# RingerPro2.net
KiCad netlist of a schematic drawn in EAGLE
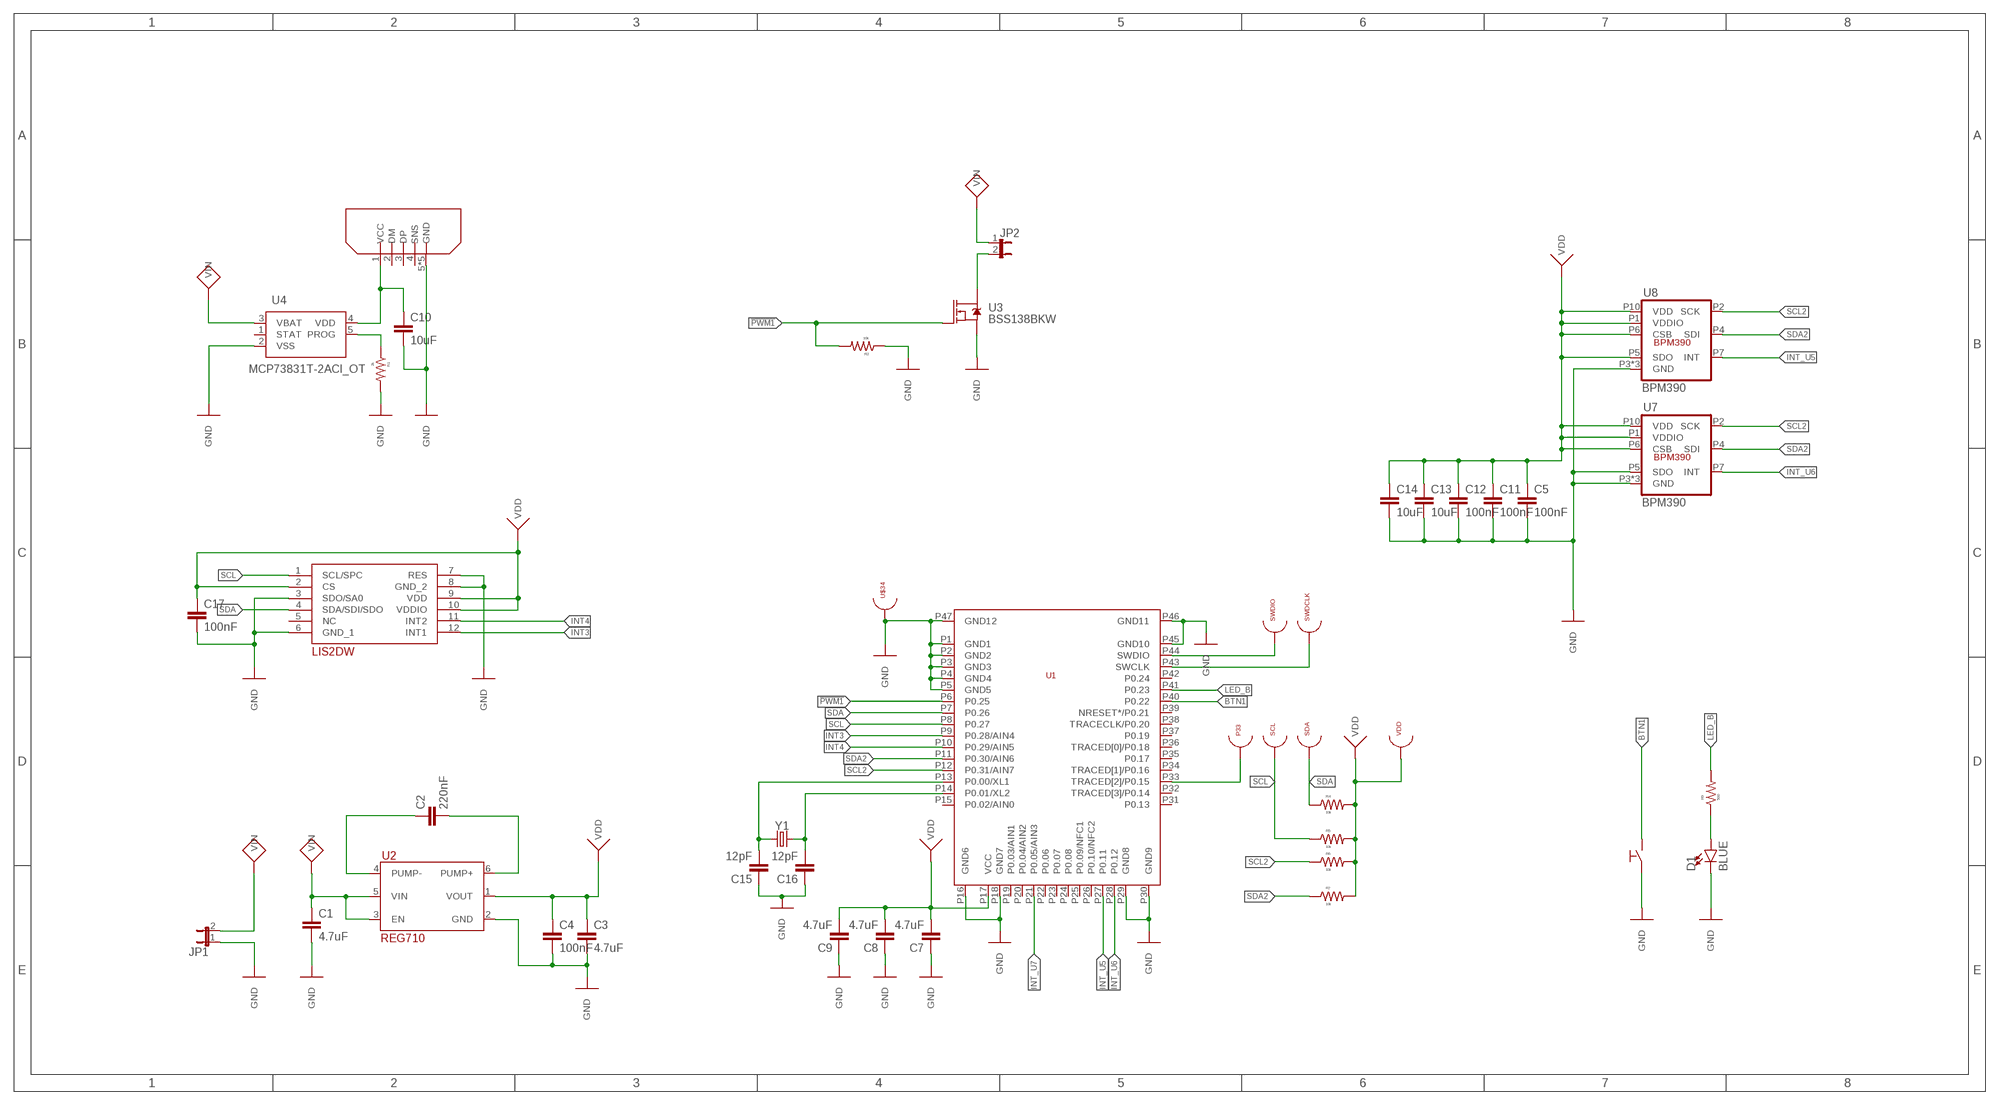
[diagram p0: schematic, sheet 1]

(export (version "E")
  (design (tool "Eeschema 10.0.6"))
  (components
    (comp (ref "C1")
      (value "4.7uF")
      (footprint "eagle-import:C0603")
      (libsource (lib "eagle-import") (part "CAPACITOR0603"))
    )
    (comp (ref "C2")
      (value "220nF")
      (footprint "eagle-import:C0603")
      (libsource (lib "eagle-import") (part "CAPACITOR0603"))
    )
    (comp (ref "C3")
      (value "4.7uF")
      (footprint "eagle-import:C0603")
      (libsource (lib "eagle-import") (part "CAPACITOR0603"))
    )
    (comp (ref "C4")
      (value "100nF")
      (footprint "eagle-import:C0603")
      (libsource (lib "eagle-import") (part "CAPACITOR0603"))
    )
    (comp (ref "C5")
      (value "100nF")
      (footprint "eagle-import:C0603")
      (libsource (lib "eagle-import") (part "CAPACITOR0603"))
    )
    (comp (ref "C7")
      (value "4.7uF")
      (footprint "eagle-import:C0603")
      (libsource (lib "eagle-import") (part "CAPACITOR0603"))
    )
    (comp (ref "C8")
      (value "4.7uF")
      (footprint "eagle-import:C0603")
      (libsource (lib "eagle-import") (part "CAPACITOR0603"))
    )
    (comp (ref "C9")
      (value "4.7uF")
      (footprint "eagle-import:C0603")
      (libsource (lib "eagle-import") (part "CAPACITOR0603"))
    )
    (comp (ref "C10")
      (value "10uF")
      (footprint "eagle-import:C0603")
      (libsource (lib "eagle-import") (part "CAPACITOR0603"))
    )
    (comp (ref "C11")
      (value "100nF")
      (footprint "eagle-import:C0603")
      (libsource (lib "eagle-import") (part "CAPACITOR0603"))
    )
    (comp (ref "C12")
      (value "100nF")
      (footprint "eagle-import:C0603")
      (libsource (lib "eagle-import") (part "CAPACITOR0603"))
    )
    (comp (ref "C13")
      (value "10uF")
      (footprint "eagle-import:C0603")
      (libsource (lib "eagle-import") (part "CAPACITOR0603"))
    )
    (comp (ref "C14")
      (value "10uF")
      (footprint "eagle-import:C0603")
      (libsource (lib "eagle-import") (part "CAPACITOR0603"))
    )
    (comp (ref "C15")
      (value "12pF")
      (footprint "eagle-import:C0603")
      (libsource (lib "eagle-import") (part "CAPACITOR0603"))
    )
    (comp (ref "C16")
      (value "12pF")
      (footprint "eagle-import:C0603")
      (libsource (lib "eagle-import") (part "CAPACITOR0603"))
    )
    (comp (ref "C17")
      (value "100nF")
      (footprint "eagle-import:C0603")
      (libsource (lib "eagle-import") (part "CAPACITOR0603"))
    )
    (comp (ref "D1")
      (value "BLUE")
      (footprint "eagle-import:LED-0603")
      (libsource (lib "eagle-import") (part "LED-BLUE0603"))
    )
    (comp (ref "IC1")
      (value "LIS2DW12TR")
      (footprint "eagle-import:LGA-12")
      (fields (field (name "MOUSER_PART_NUMBER") "511-LIS2DW12TR"))
      (libsource (lib "eagle-import") (part "LIS2DW12TR"))
    )
    (comp (ref "JP1")
      (value "JP1E")
      (footprint "eagle-import:JP1")
      (libsource (lib "eagle-import") (part "JP1E"))
    )
    (comp (ref "JP2")
      (value "JP1E")
      (footprint "eagle-import:JP1")
      (libsource (lib "eagle-import") (part "JP1E"))
    )
    (comp (ref "P33")
      (value "TESTPOINT_22")
      (footprint "eagle-import:TESTPOINT_22")
      (libsource (lib "eagle-import") (part "TESTPOINT_22"))
    )
    (comp (ref "R1")
      (value "2k")
      (footprint "eagle-import:R0603")
      (libsource (lib "eagle-import") (part "RESISTOR0603"))
    )
    (comp (ref "R2")
      (value "10k")
      (footprint "eagle-import:R0603")
      (libsource (lib "eagle-import") (part "RESISTOR0603"))
    )
    (comp (ref "R4")
      (value "10k")
      (footprint "eagle-import:R0603")
      (libsource (lib "eagle-import") (part "RESISTOR0603"))
    )
    (comp (ref "R5")
      (value "10k")
      (footprint "eagle-import:R0603")
      (libsource (lib "eagle-import") (part "RESISTOR0603"))
    )
    (comp (ref "R6")
      (value "10k")
      (footprint "eagle-import:R0603")
      (libsource (lib "eagle-import") (part "RESISTOR0603"))
    )
    (comp (ref "R7")
      (value "10k")
      (footprint "eagle-import:R0603")
      (libsource (lib "eagle-import") (part "RESISTOR0603"))
    )
    (comp (ref "R9")
      (value "500")
      (footprint "eagle-import:R0603")
      (libsource (lib "eagle-import") (part "RESISTOR0603"))
    )
    (comp (ref "SCL")
      (value "TESTPOINT_22")
      (footprint "eagle-import:TESTPOINT_22")
      (libsource (lib "eagle-import") (part "TESTPOINT_22"))
    )
    (comp (ref "SDA")
      (value "TESTPOINT_22")
      (footprint "eagle-import:TESTPOINT_22")
      (libsource (lib "eagle-import") (part "TESTPOINT_22"))
    )
    (comp (ref "SPST1")
      (value "PTS526SK08")
      (footprint "eagle-import:PTS526SKG15SMTR2LFS")
      (libsource (lib "eagle-import") (part "PTS526SK08"))
    )
    (comp (ref "SWDCLK")
      (value "TESTPOINT_22")
      (footprint "eagle-import:TESTPOINT_22")
      (libsource (lib "eagle-import") (part "TESTPOINT_22"))
    )
    (comp (ref "SWDIO")
      (value "TESTPOINT_22")
      (footprint "eagle-import:TESTPOINT_22")
      (libsource (lib "eagle-import") (part "TESTPOINT_22"))
    )
    (comp (ref "U$23")
      (value "ZX80B5P")
      (footprint "eagle-import:ZX80B5P")
      (libsource (lib "eagle-import") (part "ZX80B5P"))
    )
    (comp (ref "U$34")
      (value "TESTPOINT_22")
      (footprint "eagle-import:TESTPOINT_22")
      (libsource (lib "eagle-import") (part "TESTPOINT_22"))
    )
    (comp (ref "U1")
      (value "BMD-300")
      (footprint "eagle-import:BMD-300")
      (libsource (lib "eagle-import") (part "BMD-300"))
    )
    (comp (ref "U2")
      (value "REG710")
      (footprint "eagle-import:SOT457")
      (libsource (lib "eagle-import") (part "REG710"))
    )
    (comp (ref "U3")
      (value "BSS138BKW")
      (footprint "eagle-import:SOT65P210X110-3N")
      (libsource (lib "eagle-import") (part "BSS138BKW"))
    )
    (comp (ref "U4")
      (value "MCP73831T-2ACI_OT")
      (footprint "eagle-import:SOT95P270X145-5N")
      (fields
        (field (name "MANUFACTURER_PART_NUMBER") "MCP73831T-2ACI/OT")
        (field (name "MOUSER_PART_NUMBER") "579-MCP73831T-2ACIOT")
      )
      (libsource (lib "eagle-import") (part "MCP73831T-2ACI_OT"))
    )
    (comp (ref "U7")
      (value "BPM390")
      (footprint "eagle-import:BPM390")
      (libsource (lib "eagle-import") (part "BPM390"))
    )
    (comp (ref "U8")
      (value "BPM390")
      (footprint "eagle-import:BPM390")
      (libsource (lib "eagle-import") (part "BPM390"))
    )
    (comp (ref "VDD")
      (value "TESTPOINT_22")
      (footprint "eagle-import:TESTPOINT_22")
      (libsource (lib "eagle-import") (part "TESTPOINT_22"))
    )
    (comp (ref "Y1")
      (value "CRYSTALSMD-3.2X1.5")
      (footprint "eagle-import:CRYSTAL-SMD-3.2X1.5MM")
      (libsource (lib "eagle-import") (part "CRYSTALSMD-3.2X1.5"))
    )
  )
  (nets
    (net (code "1") (name "/~{PWM1}") (class "Default")
      (node (ref "R2") (pin "2") (pinfunction "2_2") (pintype "passive"))
      (node (ref "U1") (pin "P6") (pinfunction "P0.25_P6") (pintype "bidirectional"))
      (node (ref "U3") (pin "1") (pinfunction "G_1") (pintype "bidirectional"))
    )
    (net (code "2") (name "BTN1") (class "Default")
      (node (ref "SPST1") (pin "3") (pinfunction "P$2_3") (pintype "passive"))
      (node (ref "SPST1") (pin "4") (pinfunction "P$2_4") (pintype "passive"))
      (node (ref "U1") (pin "P40") (pinfunction "P0.22_P40") (pintype "bidirectional"))
    )
    (net (code "3") (name "GND") (class "Default")
      (node (ref "C1") (pin "2") (pinfunction "2_2") (pintype "passive"))
      (node (ref "C10") (pin "2") (pinfunction "2_2") (pintype "passive"))
      (node (ref "C11") (pin "2") (pinfunction "2_2") (pintype "passive"))
      (node (ref "C12") (pin "2") (pinfunction "2_2") (pintype "passive"))
      (node (ref "C13") (pin "2") (pinfunction "2_2") (pintype "passive"))
      (node (ref "C14") (pin "2") (pinfunction "2_2") (pintype "passive"))
      (node (ref "C15") (pin "1") (pinfunction "1_1") (pintype "passive"))
      (node (ref "C16") (pin "1") (pinfunction "1_1") (pintype "passive"))
      (node (ref "C17") (pin "2") (pinfunction "2_2") (pintype "passive"))
      (node (ref "C3") (pin "2") (pinfunction "2_2") (pintype "passive"))
      (node (ref "C4") (pin "2") (pinfunction "2_2") (pintype "passive"))
      (node (ref "C5") (pin "2") (pinfunction "2_2") (pintype "passive"))
      (node (ref "C7") (pin "1") (pinfunction "1_1") (pintype "passive"))
      (node (ref "C8") (pin "1") (pinfunction "1_1") (pintype "passive"))
      (node (ref "C9") (pin "1") (pinfunction "1_1") (pintype "passive"))
      (node (ref "D1") (pin "C") (pinfunction "C_C") (pintype "passive"))
      (node (ref "IC1") (pin "3") (pinfunction "SDO/SA0_3") (pintype "bidirectional"))
      (node (ref "IC1") (pin "6") (pinfunction "GND_1_6") (pintype "bidirectional"))
      (node (ref "IC1") (pin "7") (pinfunction "RES_7") (pintype "bidirectional"))
      (node (ref "IC1") (pin "8") (pinfunction "GND_2_8") (pintype "bidirectional"))
      (node (ref "JP1") (pin "1") (pinfunction "1_1") (pintype "passive"))
      (node (ref "R1") (pin "2") (pinfunction "2_2") (pintype "passive"))
      (node (ref "R2") (pin "1") (pinfunction "1_1") (pintype "passive"))
      (node (ref "SPST1") (pin "1") (pinfunction "P$1_1") (pintype "passive"))
      (node (ref "SPST1") (pin "2") (pinfunction "P$1_2") (pintype "passive"))
      (node (ref "U$23") (pin "5") (pinfunction "GND_5") (pintype "bidirectional"))
      (node (ref "U$23") (pin "GND1") (pinfunction "GND_GND1") (pintype "bidirectional"))
      (node (ref "U$23") (pin "GND2") (pinfunction "GND_GND2") (pintype "bidirectional"))
      (node (ref "U$23") (pin "GND3") (pinfunction "GND_GND3") (pintype "bidirectional"))
      (node (ref "U$23") (pin "GND4") (pinfunction "GND_GND4") (pintype "bidirectional"))
      (node (ref "U$34") (pin "P$1") (pinfunction "P$1_P$1") (pintype "bidirectional"))
      (node (ref "U1") (pin "P1") (pinfunction "GND1_P1") (pintype "bidirectional"))
      (node (ref "U1") (pin "P16") (pinfunction "GND6_P16") (pintype "bidirectional"))
      (node (ref "U1") (pin "P18") (pinfunction "GND7_P18") (pintype "bidirectional"))
      (node (ref "U1") (pin "P2") (pinfunction "GND2_P2") (pintype "bidirectional"))
      (node (ref "U1") (pin "P29") (pinfunction "GND8_P29") (pintype "bidirectional"))
      (node (ref "U1") (pin "P3") (pinfunction "GND3_P3") (pintype "bidirectional"))
      (node (ref "U1") (pin "P30") (pinfunction "GND9_P30") (pintype "bidirectional"))
      (node (ref "U1") (pin "P4") (pinfunction "GND4_P4") (pintype "bidirectional"))
      (node (ref "U1") (pin "P45") (pinfunction "GND10_P45") (pintype "bidirectional"))
      (node (ref "U1") (pin "P46") (pinfunction "GND11_P46") (pintype "bidirectional"))
      (node (ref "U1") (pin "P47") (pinfunction "GND12_P47") (pintype "bidirectional"))
      (node (ref "U1") (pin "P5") (pinfunction "GND5_P5") (pintype "bidirectional"))
      (node (ref "U2") (pin "2") (pinfunction "GND_2") (pintype "bidirectional"))
      (node (ref "U3") (pin "2") (pinfunction "S_2") (pintype "bidirectional"))
      (node (ref "U4") (pin "2") (pinfunction "VSS_2") (pintype "bidirectional"))
      (node (ref "U7") (pin "P3") (pinfunction "GND_P3") (pintype "power_in"))
      (node (ref "U7") (pin "P5") (pinfunction "SDO_P5") (pintype "input"))
      (node (ref "U7") (pin "P8") (pinfunction "GND_P8") (pintype "power_in"))
      (node (ref "U7") (pin "P9") (pinfunction "GND_P9") (pintype "power_in"))
      (node (ref "U8") (pin "P3") (pinfunction "GND_P3") (pintype "power_in"))
      (node (ref "U8") (pin "P8") (pinfunction "GND_P8") (pintype "power_in"))
      (node (ref "U8") (pin "P9") (pinfunction "GND_P9") (pintype "power_in"))
    )
    (net (code "4") (name "INT3") (class "Default")
      (node (ref "IC1") (pin "12") (pinfunction "INT1_12") (pintype "bidirectional"))
      (node (ref "U1") (pin "P9") (pinfunction "P0.28/AIN4_P9") (pintype "bidirectional"))
    )
    (net (code "5") (name "INT4") (class "Default")
      (node (ref "IC1") (pin "11") (pinfunction "INT2_11") (pintype "bidirectional"))
      (node (ref "U1") (pin "P10") (pinfunction "P0.29/AIN5_P10") (pintype "bidirectional"))
    )
    (net (code "6") (name "INT_U5") (class "Default")
      (node (ref "U1") (pin "P27") (pinfunction "P0.11_P27") (pintype "bidirectional"))
      (node (ref "U8") (pin "P7") (pinfunction "INT_P7") (pintype "bidirectional"))
    )
    (net (code "7") (name "INT_U6") (class "Default")
      (node (ref "U1") (pin "P28") (pinfunction "P0.12_P28") (pintype "bidirectional"))
      (node (ref "U7") (pin "P7") (pinfunction "INT_P7") (pintype "bidirectional"))
    )
    (net (code "8") (name "INT_U7") (class "Default")
      (node (ref "U1") (pin "P21") (pinfunction "P0.05/AIN3_P21") (pintype "bidirectional"))
    )
    (net (code "9") (name "LED_B") (class "Default")
      (node (ref "R9") (pin "2") (pinfunction "2_2") (pintype "passive"))
      (node (ref "U1") (pin "P41") (pinfunction "P0.23_P41") (pintype "bidirectional"))
    )
    (net (code "10") (name "Net-(D1-PadA)") (class "Default")
      (node (ref "D1") (pin "A") (pinfunction "A_A") (pintype "passive"))
      (node (ref "R9") (pin "1") (pinfunction "1_1") (pintype "passive"))
    )
    (net (code "11") (name "Net-(U$23-VCC)") (class "Default")
      (node (ref "C10") (pin "1") (pinfunction "1_1") (pintype "passive"))
      (node (ref "U$23") (pin "1") (pinfunction "VCC_1") (pintype "bidirectional"))
      (node (ref "U4") (pin "4") (pinfunction "VDD_4") (pintype "bidirectional"))
    )
    (net (code "12") (name "Net-(U1-P0.00{slash}XL1)") (class "Default")
      (node (ref "C15") (pin "2") (pinfunction "2_2") (pintype "passive"))
      (node (ref "U1") (pin "P13") (pinfunction "P0.00/XL1_P13") (pintype "bidirectional"))
      (node (ref "Y1") (pin "P$1") (pinfunction "1_P$1") (pintype "passive"))
    )
    (net (code "13") (name "Net-(U1-P0.01{slash}XL2)") (class "Default")
      (node (ref "C16") (pin "2") (pinfunction "2_2") (pintype "passive"))
      (node (ref "U1") (pin "P14") (pinfunction "P0.01/XL2_P14") (pintype "bidirectional"))
      (node (ref "Y1") (pin "P$2") (pinfunction "2_P$2") (pintype "passive"))
    )
    (net (code "14") (name "Net-(U1-SWCLK)") (class "Default")
      (node (ref "SWDCLK") (pin "P$1") (pinfunction "P$1_P$1") (pintype "bidirectional"))
      (node (ref "U1") (pin "P43") (pinfunction "SWCLK_P43") (pintype "bidirectional"))
    )
    (net (code "15") (name "Net-(U1-SWDIO)") (class "Default")
      (node (ref "SWDIO") (pin "P$1") (pinfunction "P$1_P$1") (pintype "bidirectional"))
      (node (ref "U1") (pin "P44") (pinfunction "SWDIO_P44") (pintype "bidirectional"))
    )
    (net (code "16") (name "Net-(U1-TRACED[2]{slash}P0.15)") (class "Default")
      (node (ref "P33") (pin "P$1") (pinfunction "P$1_P$1") (pintype "bidirectional"))
      (node (ref "U1") (pin "P33") (pinfunction "TRACED[2]/P0.15_P33") (pintype "bidirectional"))
    )
    (net (code "17") (name "Net-(U2-PUMP+)") (class "Default")
      (node (ref "C2") (pin "2") (pinfunction "2_2") (pintype "passive"))
      (node (ref "U2") (pin "6") (pinfunction "PUMP+_6") (pintype "bidirectional"))
    )
    (net (code "18") (name "Net-(U2-PUMP-)") (class "Default")
      (node (ref "C2") (pin "1") (pinfunction "1_1") (pintype "passive"))
      (node (ref "U2") (pin "4") (pinfunction "PUMP-_4") (pintype "bidirectional"))
    )
    (net (code "19") (name "Net-(U3-D)") (class "Default")
      (node (ref "JP2") (pin "2") (pinfunction "2_2") (pintype "passive"))
      (node (ref "U3") (pin "3") (pinfunction "D_3") (pintype "bidirectional"))
    )
    (net (code "20") (name "Net-(U4-PROG)") (class "Default")
      (node (ref "R1") (pin "1") (pinfunction "1_1") (pintype "passive"))
      (node (ref "U4") (pin "5") (pinfunction "PROG_5") (pintype "bidirectional"))
    )
    (net (code "21") (name "SCL") (class "Default")
      (node (ref "IC1") (pin "1") (pinfunction "SCL/SPC_1") (pintype "bidirectional"))
      (node (ref "R5") (pin "1") (pinfunction "1_1") (pintype "passive"))
      (node (ref "SCL") (pin "P$1") (pinfunction "P$1_P$1") (pintype "bidirectional"))
      (node (ref "U1") (pin "P8") (pinfunction "P0.27_P8") (pintype "bidirectional"))
    )
    (net (code "22") (name "SCL2") (class "Default")
      (node (ref "R6") (pin "1") (pinfunction "1_1") (pintype "passive"))
      (node (ref "U1") (pin "P12") (pinfunction "P0.31/AIN7_P12") (pintype "bidirectional"))
      (node (ref "U7") (pin "P2") (pinfunction "SCK_P2") (pintype "bidirectional"))
      (node (ref "U8") (pin "P2") (pinfunction "SCK_P2") (pintype "bidirectional"))
    )
    (net (code "23") (name "SDA") (class "Default")
      (node (ref "IC1") (pin "4") (pinfunction "SDA/SDI/SDO_4") (pintype "bidirectional"))
      (node (ref "R4") (pin "1") (pinfunction "1_1") (pintype "passive"))
      (node (ref "SDA") (pin "P$1") (pinfunction "P$1_P$1") (pintype "bidirectional"))
      (node (ref "U1") (pin "P7") (pinfunction "P0.26_P7") (pintype "bidirectional"))
    )
    (net (code "24") (name "SDA2") (class "Default")
      (node (ref "R7") (pin "1") (pinfunction "1_1") (pintype "passive"))
      (node (ref "U1") (pin "P11") (pinfunction "P0.30/AIN6_P11") (pintype "bidirectional"))
      (node (ref "U7") (pin "P4") (pinfunction "SDI_P4") (pintype "bidirectional"))
      (node (ref "U8") (pin "P4") (pinfunction "SDI_P4") (pintype "bidirectional"))
    )
    (net (code "25") (name "VDD") (class "Default")
      (node (ref "C11") (pin "1") (pinfunction "1_1") (pintype "passive"))
      (node (ref "C12") (pin "1") (pinfunction "1_1") (pintype "passive"))
      (node (ref "C13") (pin "1") (pinfunction "1_1") (pintype "passive"))
      (node (ref "C14") (pin "1") (pinfunction "1_1") (pintype "passive"))
      (node (ref "C17") (pin "1") (pinfunction "1_1") (pintype "passive"))
      (node (ref "C3") (pin "1") (pinfunction "1_1") (pintype "passive"))
      (node (ref "C4") (pin "1") (pinfunction "1_1") (pintype "passive"))
      (node (ref "C5") (pin "1") (pinfunction "1_1") (pintype "passive"))
      (node (ref "C7") (pin "2") (pinfunction "2_2") (pintype "passive"))
      (node (ref "C8") (pin "2") (pinfunction "2_2") (pintype "passive"))
      (node (ref "C9") (pin "2") (pinfunction "2_2") (pintype "passive"))
      (node (ref "IC1") (pin "10") (pinfunction "VDDIO_10") (pintype "bidirectional"))
      (node (ref "IC1") (pin "2") (pinfunction "CS_2") (pintype "bidirectional"))
      (node (ref "IC1") (pin "9") (pinfunction "VDD_9") (pintype "bidirectional"))
      (node (ref "R4") (pin "2") (pinfunction "2_2") (pintype "passive"))
      (node (ref "R5") (pin "2") (pinfunction "2_2") (pintype "passive"))
      (node (ref "R6") (pin "2") (pinfunction "2_2") (pintype "passive"))
      (node (ref "R7") (pin "2") (pinfunction "2_2") (pintype "passive"))
      (node (ref "U1") (pin "P17") (pinfunction "VCC_P17") (pintype "bidirectional"))
      (node (ref "U2") (pin "1") (pinfunction "VOUT_1") (pintype "bidirectional"))
      (node (ref "U7") (pin "P1") (pinfunction "VDDIO_P1") (pintype "power_in"))
      (node (ref "U7") (pin "P10") (pinfunction "VDD_P10") (pintype "power_in"))
      (node (ref "U7") (pin "P6") (pinfunction "CSB_P6") (pintype "input"))
      (node (ref "U8") (pin "P1") (pinfunction "VDDIO_P1") (pintype "power_in"))
      (node (ref "U8") (pin "P10") (pinfunction "VDD_P10") (pintype "power_in"))
      (node (ref "U8") (pin "P5") (pinfunction "SDO_P5") (pintype "input"))
      (node (ref "U8") (pin "P6") (pinfunction "CSB_P6") (pintype "input"))
      (node (ref "VDD") (pin "P$1") (pinfunction "P$1_P$1") (pintype "bidirectional"))
    )
    (net (code "26") (name "VIN") (class "Default")
      (node (ref "C1") (pin "1") (pinfunction "1_1") (pintype "passive"))
      (node (ref "JP1") (pin "2") (pinfunction "2_2") (pintype "passive"))
      (node (ref "JP2") (pin "1") (pinfunction "1_1") (pintype "passive"))
      (node (ref "U2") (pin "3") (pinfunction "EN_3") (pintype "bidirectional"))
      (node (ref "U2") (pin "5") (pinfunction "VIN_5") (pintype "bidirectional"))
      (node (ref "U4") (pin "3") (pinfunction "VBAT_3") (pintype "bidirectional"))
    )
    (net (code "27") (name "unconnected-(IC1-NC-Pad5)") (class "Default")
      (node (ref "IC1") (pin "5") (pinfunction "NC_5") (pintype "no_connect"))
    )
    (net (code "28") (name "unconnected-(U$23-DM-Pad2)") (class "Default")
      (node (ref "U$23") (pin "2") (pinfunction "DM_2") (pintype "bidirectional"))
    )
    (net (code "29") (name "unconnected-(U$23-DP-Pad3)") (class "Default")
      (node (ref "U$23") (pin "3") (pinfunction "DP_3") (pintype "bidirectional"))
    )
    (net (code "30") (name "unconnected-(U$23-SNS-Pad4)") (class "Default")
      (node (ref "U$23") (pin "4") (pinfunction "SNS_4") (pintype "bidirectional"))
    )
    (net (code "31") (name "unconnected-(U1-NRESET*{slash}P0.21-PadP39)") (class "Default")
      (node (ref "U1") (pin "P39") (pinfunction "NRESET*/P0.21_P39") (pintype "bidirectional"))
    )
    (net (code "32") (name "unconnected-(U1-P0.02{slash}AIN0-PadP15)") (class "Default")
      (node (ref "U1") (pin "P15") (pinfunction "P0.02/AIN0_P15") (pintype "bidirectional"))
    )
    (net (code "33") (name "unconnected-(U1-P0.03{slash}AIN1-PadP19)") (class "Default")
      (node (ref "U1") (pin "P19") (pinfunction "P0.03/AIN1_P19") (pintype "bidirectional"))
    )
    (net (code "34") (name "unconnected-(U1-P0.04{slash}AIN2-PadP20)") (class "Default")
      (node (ref "U1") (pin "P20") (pinfunction "P0.04/AIN2_P20") (pintype "bidirectional"))
    )
    (net (code "35") (name "unconnected-(U1-P0.06-PadP22)") (class "Default")
      (node (ref "U1") (pin "P22") (pinfunction "P0.06_P22") (pintype "bidirectional"))
    )
    (net (code "36") (name "unconnected-(U1-P0.07-PadP23)") (class "Default")
      (node (ref "U1") (pin "P23") (pinfunction "P0.07_P23") (pintype "bidirectional"))
    )
    (net (code "37") (name "unconnected-(U1-P0.08-PadP24)") (class "Default")
      (node (ref "U1") (pin "P24") (pinfunction "P0.08_P24") (pintype "bidirectional"))
    )
    (net (code "38") (name "unconnected-(U1-P0.09{slash}NFC1-PadP25)") (class "Default")
      (node (ref "U1") (pin "P25") (pinfunction "P0.09/NFC1_P25") (pintype "bidirectional"))
    )
    (net (code "39") (name "unconnected-(U1-P0.10{slash}NFC2-PadP26)") (class "Default")
      (node (ref "U1") (pin "P26") (pinfunction "P0.10/NFC2_P26") (pintype "bidirectional"))
    )
    (net (code "40") (name "unconnected-(U1-P0.13-PadP31)") (class "Default")
      (node (ref "U1") (pin "P31") (pinfunction "P0.13_P31") (pintype "bidirectional"))
    )
    (net (code "41") (name "unconnected-(U1-P0.17-PadP35)") (class "Default")
      (node (ref "U1") (pin "P35") (pinfunction "P0.17_P35") (pintype "bidirectional"))
    )
    (net (code "42") (name "unconnected-(U1-P0.19-PadP37)") (class "Default")
      (node (ref "U1") (pin "P37") (pinfunction "P0.19_P37") (pintype "bidirectional"))
    )
    (net (code "43") (name "unconnected-(U1-P0.24-PadP42)") (class "Default")
      (node (ref "U1") (pin "P42") (pinfunction "P0.24_P42") (pintype "bidirectional"))
    )
    (net (code "44") (name "unconnected-(U1-TRACECLK{slash}P0.20-PadP38)") (class "Default")
      (node (ref "U1") (pin "P38") (pinfunction "TRACECLK/P0.20_P38") (pintype "bidirectional"))
    )
    (net (code "45") (name "unconnected-(U1-TRACED[0]{slash}P0.18-PadP36)") (class "Default")
      (node (ref "U1") (pin "P36") (pinfunction "TRACED[0]/P0.18_P36") (pintype "bidirectional"))
    )
    (net (code "46") (name "unconnected-(U1-TRACED[1]{slash}P0.16-PadP34)") (class "Default")
      (node (ref "U1") (pin "P34") (pinfunction "TRACED[1]/P0.16_P34") (pintype "bidirectional"))
    )
    (net (code "47") (name "unconnected-(U1-TRACED[3]{slash}P0.14-PadP32)") (class "Default")
      (node (ref "U1") (pin "P32") (pinfunction "TRACED[3]/P0.14_P32") (pintype "bidirectional"))
    )
    (net (code "48") (name "unconnected-(U4-STAT-Pad1)") (class "Default")
      (node (ref "U4") (pin "1") (pinfunction "STAT_1") (pintype "bidirectional"))
    )
  )
)
